# blds.net
KiCad netlist of a schematic drawn in Altium Designer
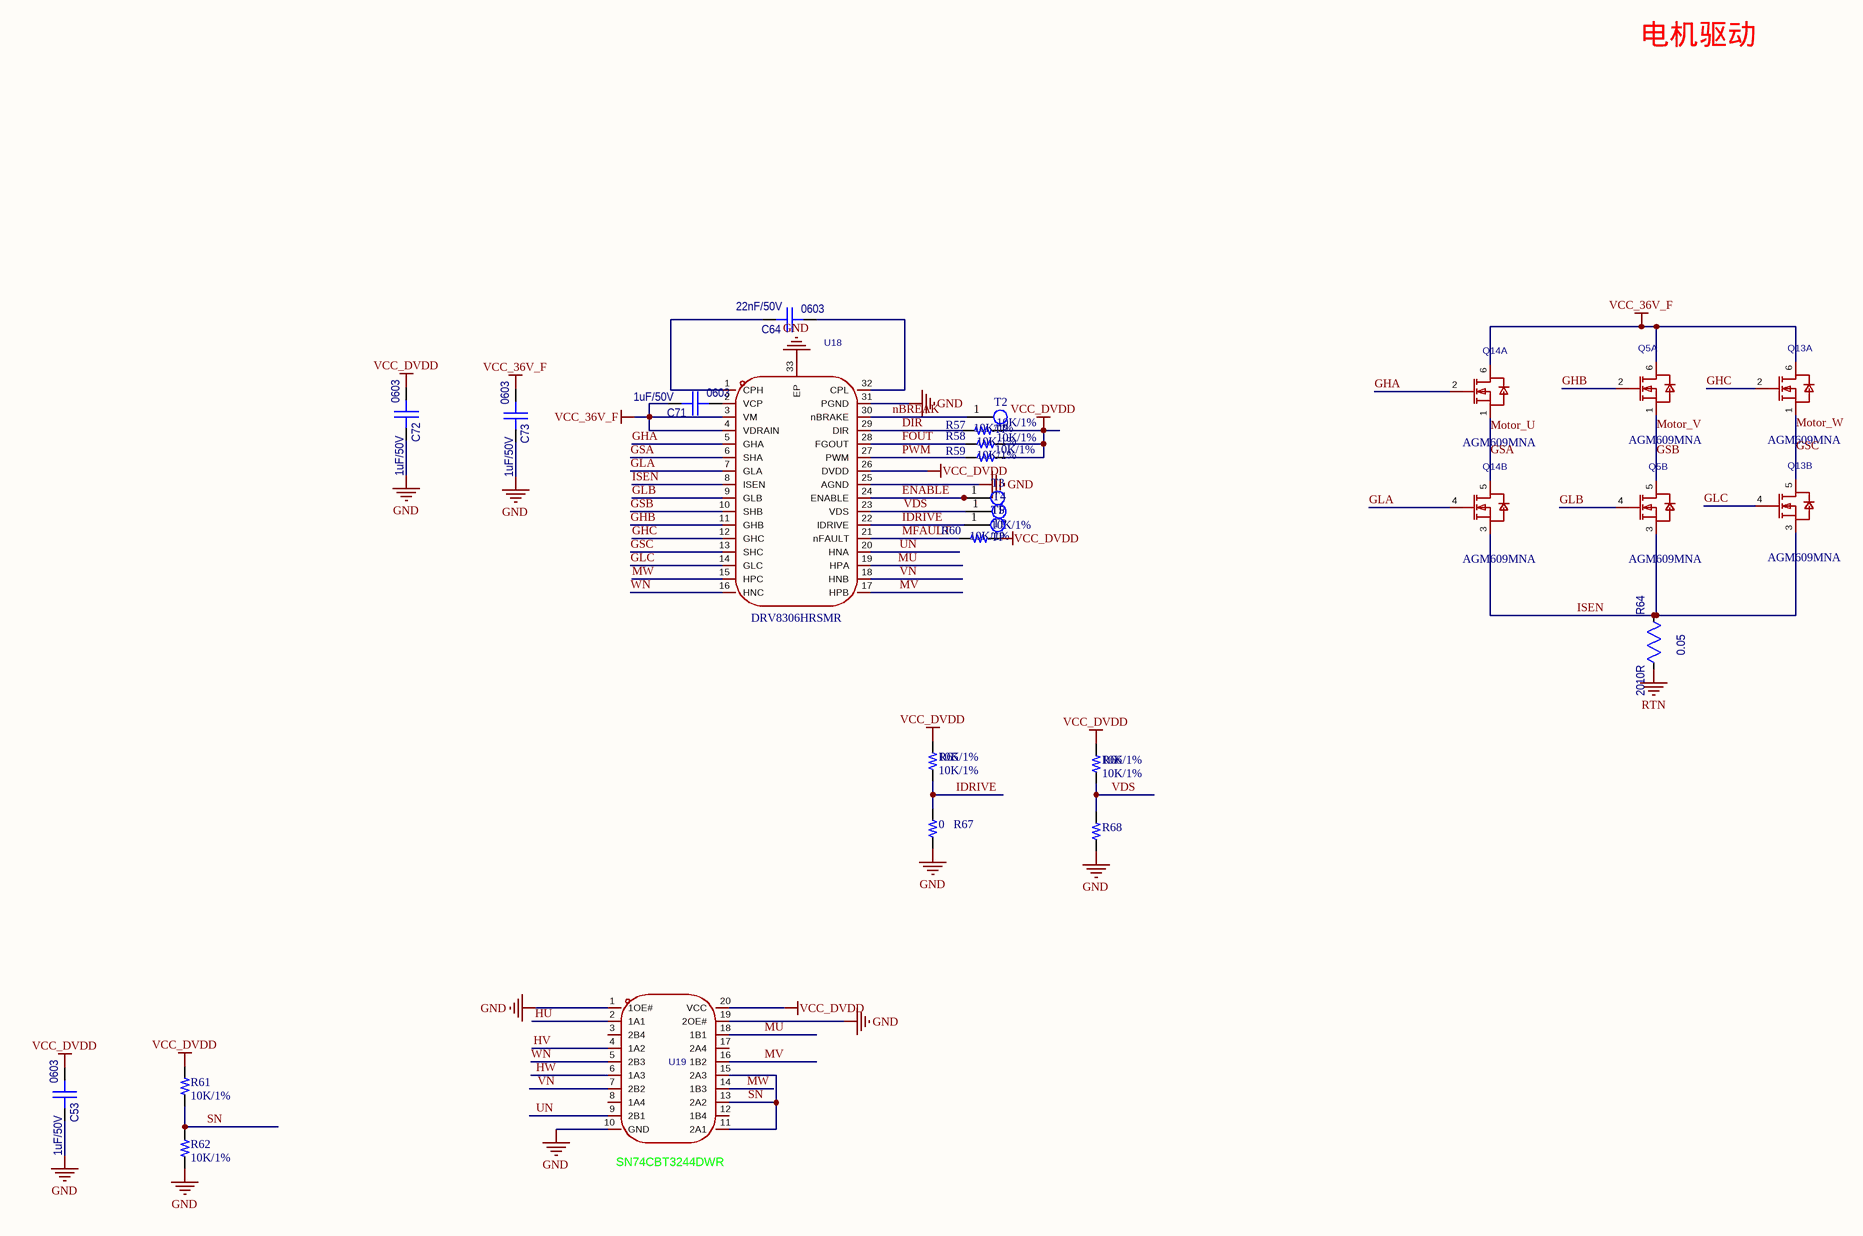
[diagram p0: blds.SchDoc]

(export (version "E")
  (design (tool "Eeschema 10.0.6"))
  (components
    (comp (ref "C53")
      (value "1uF/50V")
      (footprint "0603C")
      (description "Capacitor, MLCC")
      (fields (field (name "PACKAGE") "0603"))
      (libsource (lib "Karl") (part "Capacitor_0603"))
    )
    (comp (ref "C64")
      (value "22nF/50V")
      (footprint "0603c")
      (description "Capacitor, MLCC")
      (fields (field (name "PACKAGE") "0603"))
      (libsource (lib "Karl") (part "Capacitor_0603"))
    )
    (comp (ref "C71")
      (value "1uF/50V")
      (footprint "0603C")
      (description "Capacitor, MLCC")
      (fields (field (name "PACKAGE") "0603"))
      (libsource (lib "Karl") (part "Capacitor_0603"))
    )
    (comp (ref "C72")
      (value "1uF/50V")
      (footprint "0603C")
      (description "Capacitor, MLCC")
      (fields (field (name "PACKAGE") "0603"))
      (libsource (lib "Karl") (part "Capacitor_0603"))
    )
    (comp (ref "C73")
      (value "1uF/50V")
      (footprint "0603C")
      (description "Capacitor, MLCC")
      (fields (field (name "PACKAGE") "0603"))
      (libsource (lib "Karl") (part "Capacitor_0603"))
    )
    (comp (ref "Q5")
      (value "AGM609MNA")
      (footprint "DFN-8_L5.5-W5.2-P1.27-LS6.0-BL-EP2")
      (libsource (lib "altium-import") (part "root_0_AGM609MNA_"))
    )
    (comp (ref "Q13")
      (value "AGM609MNA")
      (footprint "DFN-8_L5.5-W5.2-P1.27-LS6.0-BL-EP2")
      (libsource (lib "altium-import") (part "root_0_AGM609MNA_"))
    )
    (comp (ref "Q14")
      (value "AGM609MNA")
      (footprint "DFN-8_L5.5-W5.2-P1.27-LS6.0-BL-EP2")
      (libsource (lib "altium-import") (part "root_0_AGM609MNA_"))
    )
    (comp (ref "R57")
      (value "10K/1%")
      (footprint "0603R")
      (fields (field (name "ALTIUM_VALUE") "10K/1%"))
      (libsource (lib "JRJ_1") (part "R"))
    )
    (comp (ref "R58")
      (value "10K/1%")
      (footprint "0603R")
      (fields (field (name "ALTIUM_VALUE") "10K/1%"))
      (libsource (lib "JRJ_1") (part "R"))
    )
    (comp (ref "R59")
      (value "10K/1%")
      (footprint "0603R")
      (fields (field (name "ALTIUM_VALUE") "10K/1%"))
      (libsource (lib "JRJ_1") (part "R"))
    )
    (comp (ref "R60")
      (value "10K/1%")
      (footprint "0603R")
      (fields (field (name "ALTIUM_VALUE") "10K/1%"))
      (libsource (lib "JRJ_1") (part "R"))
    )
    (comp (ref "R61") (value "10K/1%") (footprint "0603R") (libsource (lib "JRJ_1") (part "R")))
    (comp (ref "R62") (value "10K/1%") (footprint "0603R") (libsource (lib "JRJ_1") (part "R")))
    (comp (ref "R64")
      (value "0.05")
      (footprint "2010R")
      (description "Resistor, Standard")
      (fields (field (name "PACKAGE") "2010R"))
      (libsource (lib "Karl") (part "Resistor_0603"))
    )
    (comp (ref "R65")
      (value "10K/1%")
      (footprint "0603R")
      (fields (field (name "ALTIUM_VALUE") "10K/1%"))
      (libsource (lib "JRJ_1") (part "R"))
    )
    (comp (ref "R66")
      (value "10K/1%")
      (footprint "0603R")
      (fields (field (name "ALTIUM_VALUE") "10K/1%"))
      (libsource (lib "JRJ_1") (part "R"))
    )
    (comp (ref "R67") (value "0") (footprint "0603R") (libsource (lib "JRJ_1") (part "R")))
    (comp (ref "R68") (value "0") (footprint "0603R") (libsource (lib "JRJ_1") (part "R")))
    (comp (ref "T2") (value "TP") (footprint "TPd") (libsource (lib "Schlib_20110825") (part "TP")))
    (comp (ref "T3") (value "TP") (footprint "TPd") (libsource (lib "Schlib_20110825") (part "TP")))
    (comp (ref "T4") (value "TP") (footprint "TPd") (libsource (lib "Schlib_20110825") (part "TP")))
    (comp (ref "T5") (value "TP") (footprint "TPd") (libsource (lib "Schlib_20110825") (part "TP")))
    (comp (ref "U18")
      (value "DRV8306HRSMR")
      (footprint "VQFN-32_L4.0-W4.0-P0.40-BL-EP")
      (libsource (lib "altium-import") (part "root_0_DRV8306HRSMR_"))
    )
    (comp (ref "U19")
      (value "SN74CBT3244DWR")
      (footprint "SOIC-20_L13.0-W7.6-P1.27-LS10.3-BL:SOIC-20_L13.0-W7.6-P1.27-LS10.3-BL")
      (libsource (lib "altium-import") (part "root_0_SN74CBT3244PWRE4_"))
    )
  )
  (nets
    (net (code "1") (name "/DIR") (class "Default")
      (node (ref "R57") (pin "1") (pintype "passive"))
      (node (ref "U18") (pin "29") (pinfunction "DIR_29") (pintype "passive"))
    )
    (net (code "2") (name "/ENABLE") (class "Default")
      (node (ref "T3") (pin "1") (pintype "passive"))
      (node (ref "U18") (pin "24") (pinfunction "ENABLE_24") (pintype "passive"))
    )
    (net (code "3") (name "/FOUT") (class "Default")
      (node (ref "R58") (pin "1") (pintype "passive"))
      (node (ref "U18") (pin "28") (pinfunction "FGOUT_28") (pintype "passive"))
    )
    (net (code "4") (name "/GHA") (class "Default")
      (node (ref "Q14") (pin "2") (pinfunction "G1_2") (pintype "passive"))
      (node (ref "U18") (pin "5") (pinfunction "GHA_5") (pintype "passive"))
    )
    (net (code "5") (name "/GHB") (class "Default")
      (node (ref "Q5") (pin "2") (pinfunction "G1_2") (pintype "passive"))
      (node (ref "U18") (pin "11") (pinfunction "GHB_11") (pintype "passive"))
    )
    (net (code "6") (name "/GHC") (class "Default")
      (node (ref "Q13") (pin "2") (pinfunction "G1_2") (pintype "passive"))
      (node (ref "U18") (pin "12") (pinfunction "GHC_12") (pintype "passive"))
    )
    (net (code "7") (name "/GLA") (class "Default")
      (node (ref "Q14") (pin "4") (pinfunction "G2_4") (pintype "passive"))
      (node (ref "U18") (pin "7") (pinfunction "GLA_7") (pintype "passive"))
    )
    (net (code "8") (name "/GLB") (class "Default")
      (node (ref "Q5") (pin "4") (pinfunction "G2_4") (pintype "passive"))
      (node (ref "U18") (pin "9") (pinfunction "GLB_9") (pintype "passive"))
    )
    (net (code "9") (name "/GLC") (class "Default")
      (node (ref "Q13") (pin "4") (pinfunction "G2_4") (pintype "passive"))
      (node (ref "U18") (pin "14") (pinfunction "GLC_14") (pintype "passive"))
    )
    (net (code "10") (name "/GSA") (class "Default")
      (node (ref "Q14") (pin "1") (pinfunction "S1_1") (pintype "passive"))
      (node (ref "Q14") (pin "5") (pinfunction "D2_5") (pintype "passive"))
      (node (ref "U18") (pin "6") (pinfunction "SHA_6") (pintype "passive"))
    )
    (net (code "11") (name "/GSB") (class "Default")
      (node (ref "Q5") (pin "1") (pinfunction "S1_1") (pintype "passive"))
      (node (ref "Q5") (pin "5") (pinfunction "D2_5") (pintype "passive"))
      (node (ref "U18") (pin "10") (pinfunction "SHB_10") (pintype "passive"))
    )
    (net (code "12") (name "/GSC") (class "Default")
      (node (ref "Q13") (pin "1") (pinfunction "S1_1") (pintype "passive"))
      (node (ref "Q13") (pin "5") (pinfunction "D2_5") (pintype "passive"))
      (node (ref "U18") (pin "13") (pinfunction "SHC_13") (pintype "passive"))
    )
    (net (code "13") (name "/HU") (class "Default")
      (node (ref "U19") (pin "2") (pinfunction "1A1_2") (pintype "passive"))
    )
    (net (code "14") (name "/HV") (class "Default")
      (node (ref "U19") (pin "4") (pinfunction "1A2_4") (pintype "passive"))
    )
    (net (code "15") (name "/HW") (class "Default")
      (node (ref "U19") (pin "6") (pinfunction "1A3_6") (pintype "passive"))
    )
    (net (code "16") (name "/IDRIVE") (class "Default")
      (node (ref "R65") (pin "2") (pintype "passive"))
      (node (ref "R67") (pin "1") (pintype "passive"))
      (node (ref "T5") (pin "1") (pintype "passive"))
      (node (ref "U18") (pin "22") (pinfunction "IDRIVE_22") (pintype "passive"))
    )
    (net (code "17") (name "/ISEN") (class "Default")
      (node (ref "Q13") (pin "3") (pinfunction "S2_3") (pintype "passive"))
      (node (ref "Q14") (pin "3") (pinfunction "S2_3") (pintype "passive"))
      (node (ref "Q5") (pin "3") (pinfunction "S2_3") (pintype "passive"))
      (node (ref "R64") (pin "2") (pinfunction "2_2") (pintype "passive"))
      (node (ref "U18") (pin "8") (pinfunction "ISEN_8") (pintype "passive"))
    )
    (net (code "18") (name "/MFAULT") (class "Default")
      (node (ref "R60") (pin "1") (pintype "passive"))
      (node (ref "U18") (pin "21") (pinfunction "nFAULT_21") (pintype "passive"))
    )
    (net (code "19") (name "/MU") (class "Default")
      (node (ref "U18") (pin "19") (pinfunction "HPA_19") (pintype "passive"))
      (node (ref "U19") (pin "18") (pinfunction "1B1_18") (pintype "passive"))
    )
    (net (code "20") (name "/MV") (class "Default")
      (node (ref "U18") (pin "17") (pinfunction "HPB_17") (pintype "passive"))
      (node (ref "U19") (pin "16") (pinfunction "1B2_16") (pintype "passive"))
    )
    (net (code "21") (name "/MW") (class "Default")
      (node (ref "U18") (pin "15") (pinfunction "HPC_15") (pintype "passive"))
      (node (ref "U19") (pin "14") (pinfunction "1B3_14") (pintype "passive"))
    )
    (net (code "22") (name "/PWM") (class "Default")
      (node (ref "R59") (pin "1") (pintype "passive"))
      (node (ref "U18") (pin "27") (pinfunction "PWM_27") (pintype "passive"))
    )
    (net (code "23") (name "/SN") (class "Default")
      (node (ref "R61") (pin "2") (pintype "passive"))
      (node (ref "R62") (pin "1") (pintype "passive"))
      (node (ref "U19") (pin "11") (pinfunction "2A1_11") (pintype "passive"))
      (node (ref "U19") (pin "13") (pinfunction "2A2_13") (pintype "passive"))
      (node (ref "U19") (pin "15") (pinfunction "2A3_15") (pintype "passive"))
    )
    (net (code "24") (name "/UN") (class "Default")
      (node (ref "U18") (pin "20") (pinfunction "HNA_20") (pintype "passive"))
      (node (ref "U19") (pin "9") (pinfunction "2B1_9") (pintype "passive"))
    )
    (net (code "25") (name "/VDS") (class "Default")
      (node (ref "R66") (pin "2") (pintype "passive"))
      (node (ref "R68") (pin "1") (pintype "passive"))
      (node (ref "T4") (pin "1") (pintype "passive"))
      (node (ref "U18") (pin "23") (pinfunction "VDS_23") (pintype "passive"))
    )
    (net (code "26") (name "/VN") (class "Default")
      (node (ref "U18") (pin "18") (pinfunction "HNB_18") (pintype "passive"))
      (node (ref "U19") (pin "7") (pinfunction "2B2_7") (pintype "passive"))
    )
    (net (code "27") (name "/WN") (class "Default")
      (node (ref "U18") (pin "16") (pinfunction "HNC_16") (pintype "passive"))
      (node (ref "U19") (pin "5") (pinfunction "2B3_5") (pintype "passive"))
    )
    (net (code "28") (name "/nBREAK") (class "Default")
      (node (ref "T2") (pin "1") (pintype "passive"))
      (node (ref "U18") (pin "30") (pinfunction "nBRAKE_30") (pintype "passive"))
    )
    (net (code "29") (name "GND") (class "Default")
      (node (ref "C53") (pin "2") (pinfunction "2_2") (pintype "passive"))
      (node (ref "C72") (pin "2") (pinfunction "2_2") (pintype "passive"))
      (node (ref "C73") (pin "2") (pinfunction "2_2") (pintype "passive"))
      (node (ref "R62") (pin "2") (pintype "passive"))
      (node (ref "R67") (pin "2") (pintype "passive"))
      (node (ref "R68") (pin "2") (pintype "passive"))
      (node (ref "U18") (pin "25") (pinfunction "AGND_25") (pintype "passive"))
      (node (ref "U18") (pin "31") (pinfunction "PGND_31") (pintype "passive"))
      (node (ref "U18") (pin "33") (pinfunction "EP_33") (pintype "passive"))
      (node (ref "U19") (pin "1") (pinfunction "1OE#_1") (pintype "passive"))
      (node (ref "U19") (pin "10") (pinfunction "GND_10") (pintype "passive"))
      (node (ref "U19") (pin "19") (pinfunction "2OE#_19") (pintype "passive"))
    )
    (net (code "30") (name "Net-(U18-CPH)") (class "Default")
      (node (ref "C64") (pin "2") (pinfunction "2_2") (pintype "passive"))
      (node (ref "U18") (pin "1") (pinfunction "CPH_1") (pintype "passive"))
    )
    (net (code "31") (name "Net-(U18-CPL)") (class "Default")
      (node (ref "C64") (pin "1") (pinfunction "1_1") (pintype "passive"))
      (node (ref "U18") (pin "32") (pinfunction "CPL_32") (pintype "passive"))
    )
    (net (code "32") (name "Net-(U18-VCP)") (class "Default")
      (node (ref "C71") (pin "1") (pinfunction "1_1") (pintype "passive"))
      (node (ref "U18") (pin "2") (pinfunction "VCP_2") (pintype "passive"))
    )
    (net (code "33") (name "RTN") (class "Default")
      (node (ref "R64") (pin "1") (pinfunction "1_1") (pintype "passive"))
    )
    (net (code "34") (name "VCC_36V_F") (class "Default")
      (node (ref "C71") (pin "2") (pinfunction "2_2") (pintype "passive"))
      (node (ref "C73") (pin "1") (pinfunction "1_1") (pintype "passive"))
      (node (ref "Q13") (pin "6") (pinfunction "D1_6") (pintype "passive"))
      (node (ref "Q14") (pin "6") (pinfunction "D1_6") (pintype "passive"))
      (node (ref "Q5") (pin "6") (pinfunction "D1_6") (pintype "passive"))
      (node (ref "U18") (pin "3") (pinfunction "VM_3") (pintype "passive"))
      (node (ref "U18") (pin "4") (pinfunction "VDRAIN_4") (pintype "passive"))
    )
    (net (code "35") (name "VCC_DVDD") (class "Default")
      (node (ref "C53") (pin "1") (pinfunction "1_1") (pintype "passive"))
      (node (ref "C72") (pin "1") (pinfunction "1_1") (pintype "passive"))
      (node (ref "R57") (pin "2") (pintype "passive"))
      (node (ref "R58") (pin "2") (pintype "passive"))
      (node (ref "R59") (pin "2") (pintype "passive"))
      (node (ref "R60") (pin "2") (pintype "passive"))
      (node (ref "R61") (pin "1") (pintype "passive"))
      (node (ref "R65") (pin "1") (pintype "passive"))
      (node (ref "R66") (pin "1") (pintype "passive"))
      (node (ref "U18") (pin "26") (pinfunction "DVDD_26") (pintype "passive"))
      (node (ref "U19") (pin "20") (pinfunction "VCC_20") (pintype "passive"))
    )
    (net (code "36") (name "unconnected-(U19-1A4-Pad8)") (class "Default")
      (node (ref "U19") (pin "8") (pinfunction "1A4_8") (pintype "passive"))
    )
    (net (code "37") (name "unconnected-(U19-1B4-Pad12)") (class "Default")
      (node (ref "U19") (pin "12") (pinfunction "1B4_12") (pintype "passive"))
    )
    (net (code "38") (name "unconnected-(U19-2A4-Pad17)") (class "Default")
      (node (ref "U19") (pin "17") (pinfunction "2A4_17") (pintype "passive"))
    )
    (net (code "39") (name "unconnected-(U19-2B4-Pad3)") (class "Default")
      (node (ref "U19") (pin "3") (pinfunction "2B4_3") (pintype "passive"))
    )
  )
)
